# DO_module.net
KiCad netlist of a schematic drawn in EAGLE
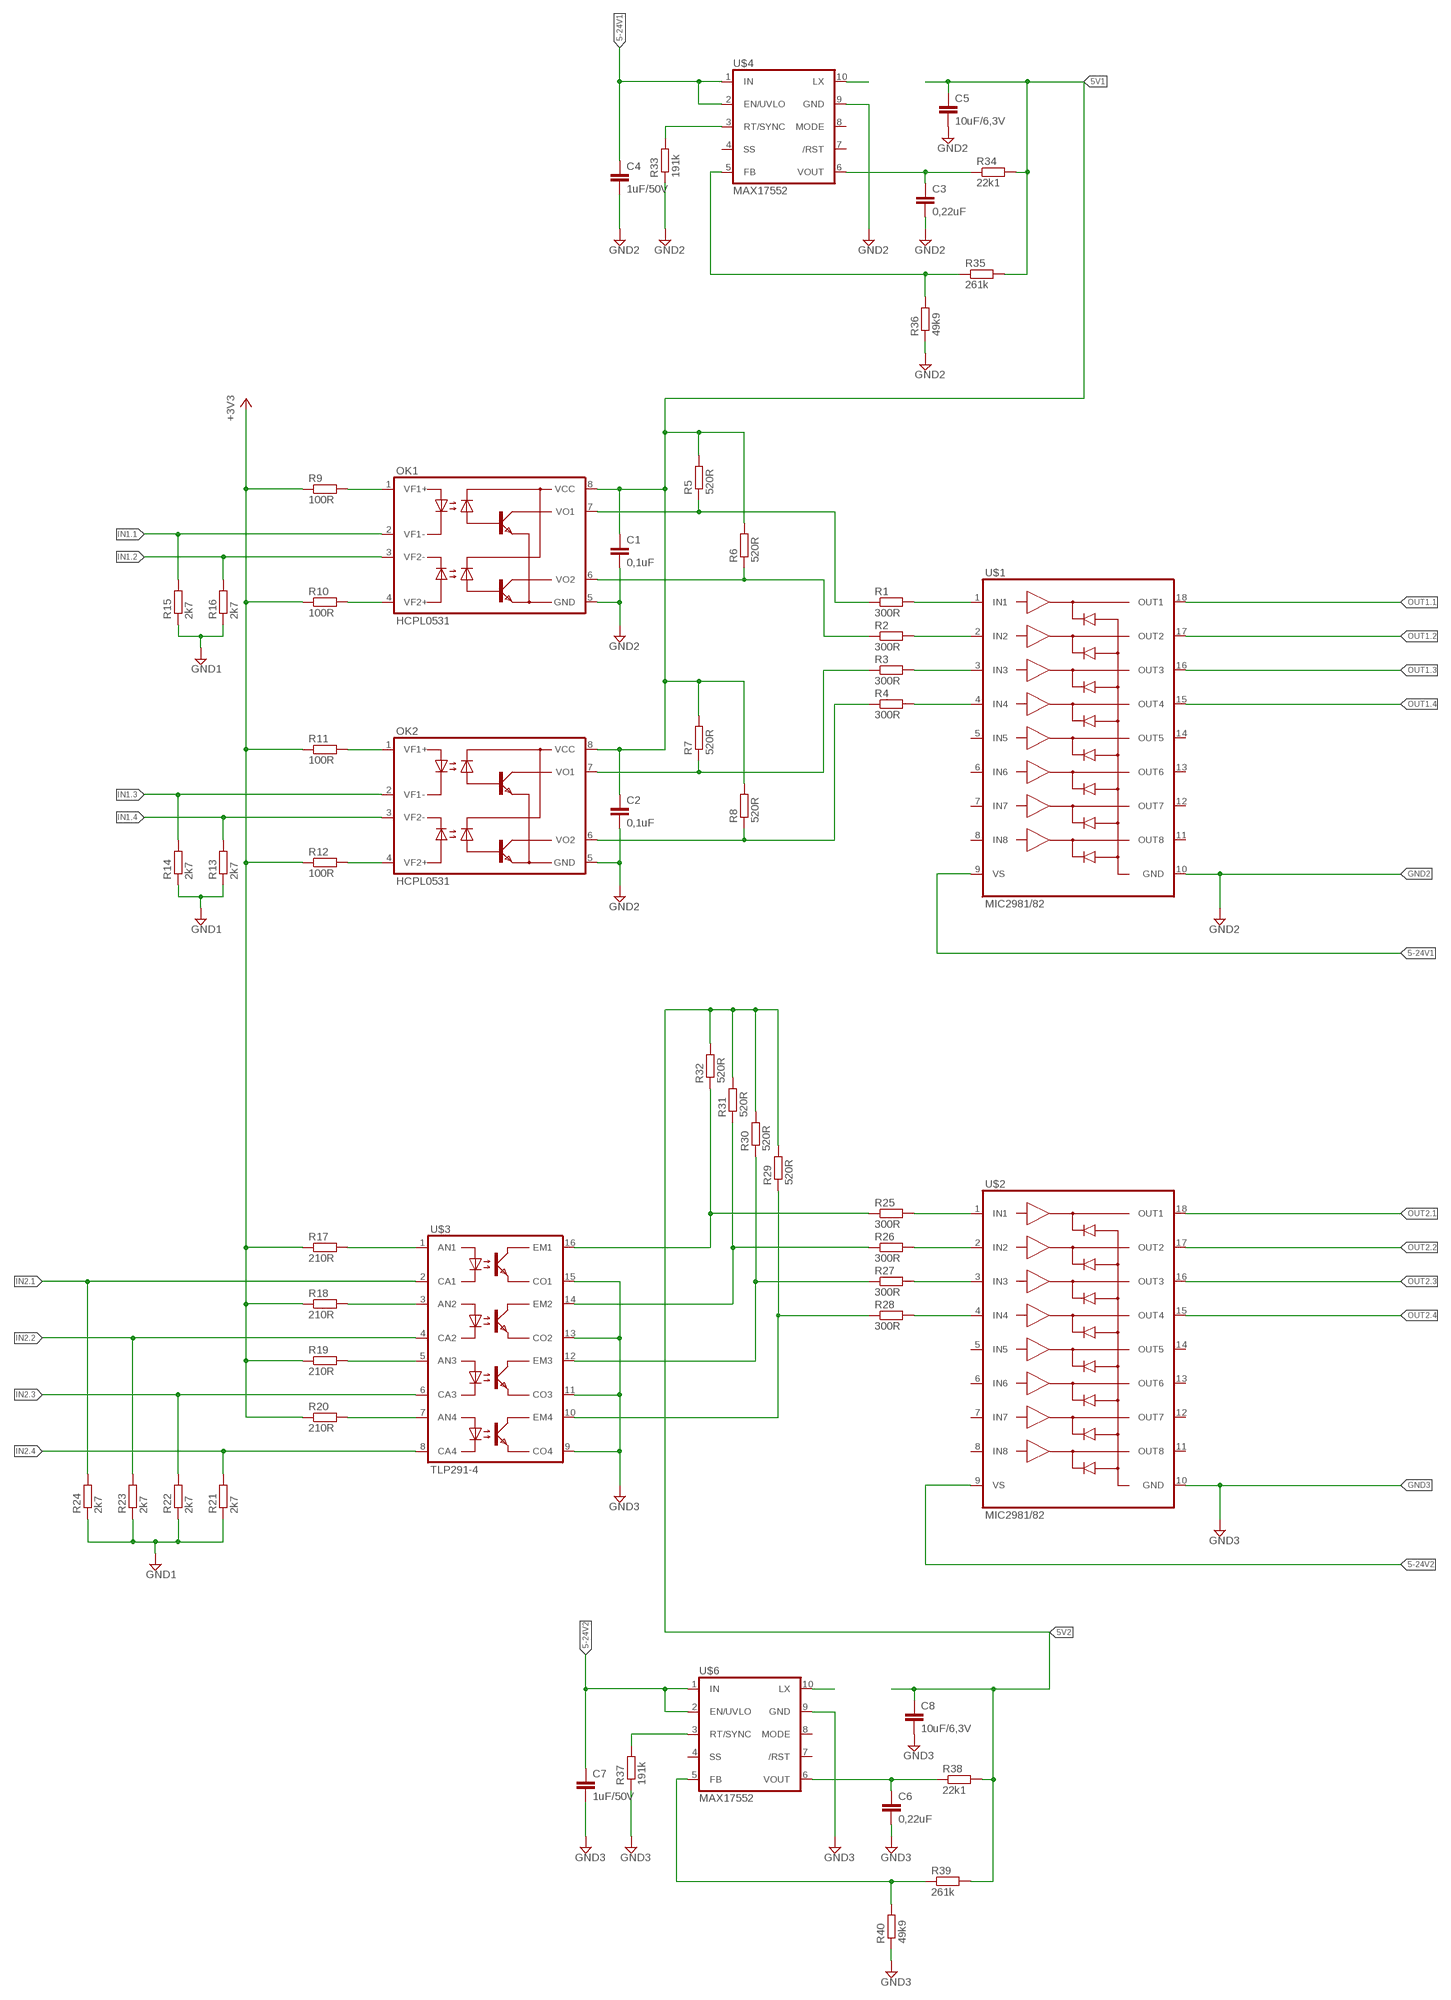
[diagram p0: schematic, sheet 1]

(export (version "E")
  (design (tool "Eeschema 10.0.6"))
  (components
    (comp (ref "C1")
      (value "0,1uF")
      (footprint "eagle-import:C0603")
      (libsource (lib "eagle-import") (part "C-EUC0603"))
    )
    (comp (ref "C2")
      (value "0,1uF")
      (footprint "eagle-import:C0603")
      (libsource (lib "eagle-import") (part "C-EUC0603"))
    )
    (comp (ref "C3")
      (value "0,22uF")
      (footprint "eagle-import:C0603")
      (libsource (lib "eagle-import") (part "C-EUC0603"))
    )
    (comp (ref "C4")
      (value "1uF/50V")
      (footprint "eagle-import:C1206")
      (libsource (lib "eagle-import") (part "C-EUC1206"))
    )
    (comp (ref "C5")
      (value "10uF/6,3V")
      (footprint "eagle-import:C1206")
      (libsource (lib "eagle-import") (part "C-EUC1206"))
    )
    (comp (ref "C6")
      (value "0,22uF")
      (footprint "eagle-import:C0603")
      (libsource (lib "eagle-import") (part "C-EUC0603"))
    )
    (comp (ref "C7")
      (value "1uF/50V")
      (footprint "eagle-import:C1206")
      (libsource (lib "eagle-import") (part "C-EUC1206"))
    )
    (comp (ref "C8")
      (value "10uF/6,3V")
      (footprint "eagle-import:C1206")
      (libsource (lib "eagle-import") (part "C-EUC1206"))
    )
    (comp (ref "OK1")
      (value "HCPL0531")
      (footprint "eagle-import:SOIC08")
      (libsource (lib "eagle-import") (part "HCPL0531"))
    )
    (comp (ref "OK2")
      (value "HCPL0531")
      (footprint "eagle-import:SOIC08")
      (libsource (lib "eagle-import") (part "HCPL0531"))
    )
    (comp (ref "R1")
      (value "300R")
      (footprint "eagle-import:R0603")
      (libsource (lib "eagle-import") (part "R-EU_R0603"))
    )
    (comp (ref "R2")
      (value "300R")
      (footprint "eagle-import:R0603")
      (libsource (lib "eagle-import") (part "R-EU_R0603"))
    )
    (comp (ref "R3")
      (value "300R")
      (footprint "eagle-import:R0603")
      (libsource (lib "eagle-import") (part "R-EU_R0603"))
    )
    (comp (ref "R4")
      (value "300R")
      (footprint "eagle-import:R0603")
      (libsource (lib "eagle-import") (part "R-EU_R0603"))
    )
    (comp (ref "R5")
      (value "520R")
      (footprint "eagle-import:R0603")
      (libsource (lib "eagle-import") (part "R-EU_R0603"))
    )
    (comp (ref "R6")
      (value "520R")
      (footprint "eagle-import:R0603")
      (libsource (lib "eagle-import") (part "R-EU_R0603"))
    )
    (comp (ref "R7")
      (value "520R")
      (footprint "eagle-import:R0603")
      (libsource (lib "eagle-import") (part "R-EU_R0603"))
    )
    (comp (ref "R8")
      (value "520R")
      (footprint "eagle-import:R0603")
      (libsource (lib "eagle-import") (part "R-EU_R0603"))
    )
    (comp (ref "R9")
      (value "100R")
      (footprint "eagle-import:R0603")
      (libsource (lib "eagle-import") (part "R-EU_R0603"))
    )
    (comp (ref "R10")
      (value "100R")
      (footprint "eagle-import:R0603")
      (libsource (lib "eagle-import") (part "R-EU_R0603"))
    )
    (comp (ref "R11")
      (value "100R")
      (footprint "eagle-import:R0603")
      (libsource (lib "eagle-import") (part "R-EU_R0603"))
    )
    (comp (ref "R12")
      (value "100R")
      (footprint "eagle-import:R0603")
      (libsource (lib "eagle-import") (part "R-EU_R0603"))
    )
    (comp (ref "R13")
      (value "2k7")
      (footprint "eagle-import:R0603")
      (libsource (lib "eagle-import") (part "R-EU_R0603"))
    )
    (comp (ref "R14")
      (value "2k7")
      (footprint "eagle-import:R0603")
      (libsource (lib "eagle-import") (part "R-EU_R0603"))
    )
    (comp (ref "R15")
      (value "2k7")
      (footprint "eagle-import:R0603")
      (libsource (lib "eagle-import") (part "R-EU_R0603"))
    )
    (comp (ref "R16")
      (value "2k7")
      (footprint "eagle-import:R0603")
      (libsource (lib "eagle-import") (part "R-EU_R0603"))
    )
    (comp (ref "R17")
      (value "210R")
      (footprint "eagle-import:R0603")
      (libsource (lib "eagle-import") (part "R-EU_R0603"))
    )
    (comp (ref "R18")
      (value "210R")
      (footprint "eagle-import:R0603")
      (libsource (lib "eagle-import") (part "R-EU_R0603"))
    )
    (comp (ref "R19")
      (value "210R")
      (footprint "eagle-import:R0603")
      (libsource (lib "eagle-import") (part "R-EU_R0603"))
    )
    (comp (ref "R20")
      (value "210R")
      (footprint "eagle-import:R0603")
      (libsource (lib "eagle-import") (part "R-EU_R0603"))
    )
    (comp (ref "R21")
      (value "2k7")
      (footprint "eagle-import:R0603")
      (libsource (lib "eagle-import") (part "R-EU_R0603"))
    )
    (comp (ref "R22")
      (value "2k7")
      (footprint "eagle-import:R0603")
      (libsource (lib "eagle-import") (part "R-EU_R0603"))
    )
    (comp (ref "R23")
      (value "2k7")
      (footprint "eagle-import:R0603")
      (libsource (lib "eagle-import") (part "R-EU_R0603"))
    )
    (comp (ref "R24")
      (value "2k7")
      (footprint "eagle-import:R0603")
      (libsource (lib "eagle-import") (part "R-EU_R0603"))
    )
    (comp (ref "R25")
      (value "300R")
      (footprint "eagle-import:R0603")
      (libsource (lib "eagle-import") (part "R-EU_R0603"))
    )
    (comp (ref "R26")
      (value "300R")
      (footprint "eagle-import:R0603")
      (libsource (lib "eagle-import") (part "R-EU_R0603"))
    )
    (comp (ref "R27")
      (value "300R")
      (footprint "eagle-import:R0603")
      (libsource (lib "eagle-import") (part "R-EU_R0603"))
    )
    (comp (ref "R28")
      (value "300R")
      (footprint "eagle-import:R0603")
      (libsource (lib "eagle-import") (part "R-EU_R0603"))
    )
    (comp (ref "R29")
      (value "520R")
      (footprint "eagle-import:R0603")
      (libsource (lib "eagle-import") (part "R-EU_R0603"))
    )
    (comp (ref "R30")
      (value "520R")
      (footprint "eagle-import:R0603")
      (libsource (lib "eagle-import") (part "R-EU_R0603"))
    )
    (comp (ref "R31")
      (value "520R")
      (footprint "eagle-import:R0603")
      (libsource (lib "eagle-import") (part "R-EU_R0603"))
    )
    (comp (ref "R32")
      (value "520R")
      (footprint "eagle-import:R0603")
      (libsource (lib "eagle-import") (part "R-EU_R0603"))
    )
    (comp (ref "R33")
      (value "191k")
      (footprint "eagle-import:R0603")
      (libsource (lib "eagle-import") (part "R-EU_R0603"))
    )
    (comp (ref "R34")
      (value "22k1")
      (footprint "eagle-import:R0603")
      (libsource (lib "eagle-import") (part "R-EU_R0603"))
    )
    (comp (ref "R35")
      (value "261k")
      (footprint "eagle-import:R0603")
      (libsource (lib "eagle-import") (part "R-EU_R0603"))
    )
    (comp (ref "R36")
      (value "49k9")
      (footprint "eagle-import:R0603")
      (libsource (lib "eagle-import") (part "R-EU_R0603"))
    )
    (comp (ref "R37")
      (value "191k")
      (footprint "eagle-import:R0603")
      (libsource (lib "eagle-import") (part "R-EU_R0603"))
    )
    (comp (ref "R38")
      (value "22k1")
      (footprint "eagle-import:R0603")
      (libsource (lib "eagle-import") (part "R-EU_R0603"))
    )
    (comp (ref "R39")
      (value "261k")
      (footprint "eagle-import:R0603")
      (libsource (lib "eagle-import") (part "R-EU_R0603"))
    )
    (comp (ref "R40")
      (value "49k9")
      (footprint "eagle-import:R0603")
      (libsource (lib "eagle-import") (part "R-EU_R0603"))
    )
    (comp (ref "U$1")
      (value "MIC2981/82")
      (footprint "eagle-import:SOP18")
      (libsource (lib "eagle-import") (part "MIC2981/82"))
    )
    (comp (ref "U$2")
      (value "MIC2981/82")
      (footprint "eagle-import:SOP18")
      (libsource (lib "eagle-import") (part "MIC2981/82"))
    )
    (comp (ref "U$3")
      (value "TLP291-4")
      (footprint "eagle-import:SO16")
      (libsource (lib "eagle-import") (part "TLP291-4"))
    )
    (comp (ref "U$4")
      (value "MAX17552")
      (footprint "eagle-import:TSSOP-10(10UMAX)")
      (libsource (lib "eagle-import") (part "MAX17552"))
    )
    (comp (ref "U$6")
      (value "MAX17552")
      (footprint "eagle-import:TSSOP-10(10UMAX)")
      (libsource (lib "eagle-import") (part "MAX17552"))
    )
  )
  (nets
    (net (code "1") (name "+3V3") (class "Default")
      (node (ref "R10") (pin "1") (pinfunction "1_1") (pintype "passive"))
      (node (ref "R11") (pin "1") (pinfunction "1_1") (pintype "passive"))
      (node (ref "R12") (pin "1") (pinfunction "1_1") (pintype "passive"))
      (node (ref "R17") (pin "1") (pinfunction "1_1") (pintype "passive"))
      (node (ref "R18") (pin "1") (pinfunction "1_1") (pintype "passive"))
      (node (ref "R19") (pin "1") (pinfunction "1_1") (pintype "passive"))
      (node (ref "R20") (pin "1") (pinfunction "1_1") (pintype "passive"))
      (node (ref "R9") (pin "1") (pinfunction "1_1") (pintype "passive"))
    )
    (net (code "2") (name "5-24V1") (class "Default")
      (node (ref "C4") (pin "1") (pinfunction "1_1") (pintype "passive"))
      (node (ref "U$1") (pin "9") (pinfunction "VS_9") (pintype "passive"))
      (node (ref "U$4") (pin "1") (pinfunction "IN_1") (pintype "power_in"))
      (node (ref "U$4") (pin "2") (pinfunction "EN/UVLO_2") (pintype "input"))
    )
    (net (code "3") (name "5-24V2") (class "Default")
      (node (ref "C7") (pin "1") (pinfunction "1_1") (pintype "passive"))
      (node (ref "U$2") (pin "9") (pinfunction "VS_9") (pintype "passive"))
      (node (ref "U$6") (pin "1") (pinfunction "IN_1") (pintype "power_in"))
      (node (ref "U$6") (pin "2") (pinfunction "EN/UVLO_2") (pintype "input"))
    )
    (net (code "4") (name "5V1") (class "Default")
      (node (ref "C1") (pin "1") (pinfunction "1_1") (pintype "passive"))
      (node (ref "C2") (pin "1") (pinfunction "1_1") (pintype "passive"))
      (node (ref "C5") (pin "1") (pinfunction "1_1") (pintype "passive"))
      (node (ref "OK1") (pin "8") (pinfunction "VCC_8") (pintype "passive"))
      (node (ref "OK2") (pin "8") (pinfunction "VCC_8") (pintype "passive"))
      (node (ref "R34") (pin "2") (pinfunction "2_2") (pintype "passive"))
      (node (ref "R35") (pin "2") (pinfunction "2_2") (pintype "passive"))
      (node (ref "R5") (pin "2") (pinfunction "2_2") (pintype "passive"))
      (node (ref "R6") (pin "2") (pinfunction "2_2") (pintype "passive"))
      (node (ref "R7") (pin "2") (pinfunction "2_2") (pintype "passive"))
      (node (ref "R8") (pin "2") (pinfunction "2_2") (pintype "passive"))
    )
    (net (code "5") (name "5V2") (class "Default")
      (node (ref "C8") (pin "1") (pinfunction "1_1") (pintype "passive"))
      (node (ref "R29") (pin "2") (pinfunction "2_2") (pintype "passive"))
      (node (ref "R30") (pin "2") (pinfunction "2_2") (pintype "passive"))
      (node (ref "R31") (pin "2") (pinfunction "2_2") (pintype "passive"))
      (node (ref "R32") (pin "2") (pinfunction "2_2") (pintype "passive"))
      (node (ref "R38") (pin "2") (pinfunction "2_2") (pintype "passive"))
      (node (ref "R39") (pin "2") (pinfunction "2_2") (pintype "passive"))
    )
    (net (code "6") (name "GND1") (class "Default")
      (node (ref "R13") (pin "1") (pinfunction "1_1") (pintype "passive"))
      (node (ref "R14") (pin "1") (pinfunction "1_1") (pintype "passive"))
      (node (ref "R15") (pin "1") (pinfunction "1_1") (pintype "passive"))
      (node (ref "R16") (pin "1") (pinfunction "1_1") (pintype "passive"))
      (node (ref "R21") (pin "1") (pinfunction "1_1") (pintype "passive"))
      (node (ref "R22") (pin "1") (pinfunction "1_1") (pintype "passive"))
      (node (ref "R23") (pin "1") (pinfunction "1_1") (pintype "passive"))
      (node (ref "R24") (pin "1") (pinfunction "1_1") (pintype "passive"))
    )
    (net (code "7") (name "GND2") (class "Default")
      (node (ref "C1") (pin "2") (pinfunction "2_2") (pintype "passive"))
      (node (ref "C2") (pin "2") (pinfunction "2_2") (pintype "passive"))
      (node (ref "C3") (pin "2") (pinfunction "2_2") (pintype "passive"))
      (node (ref "C4") (pin "2") (pinfunction "2_2") (pintype "passive"))
      (node (ref "C5") (pin "2") (pinfunction "2_2") (pintype "passive"))
      (node (ref "OK1") (pin "5") (pinfunction "GND_5") (pintype "passive"))
      (node (ref "OK2") (pin "5") (pinfunction "GND_5") (pintype "passive"))
      (node (ref "R33") (pin "1") (pinfunction "1_1") (pintype "passive"))
      (node (ref "R36") (pin "1") (pinfunction "1_1") (pintype "passive"))
      (node (ref "U$1") (pin "10") (pinfunction "GND_10") (pintype "passive"))
      (node (ref "U$4") (pin "9") (pinfunction "GND_9") (pintype "output"))
    )
    (net (code "8") (name "GND3") (class "Default")
      (node (ref "C6") (pin "2") (pinfunction "2_2") (pintype "passive"))
      (node (ref "C7") (pin "2") (pinfunction "2_2") (pintype "passive"))
      (node (ref "C8") (pin "2") (pinfunction "2_2") (pintype "passive"))
      (node (ref "R37") (pin "1") (pinfunction "1_1") (pintype "passive"))
      (node (ref "R40") (pin "1") (pinfunction "1_1") (pintype "passive"))
      (node (ref "U$2") (pin "10") (pinfunction "GND_10") (pintype "passive"))
      (node (ref "U$3") (pin "11") (pinfunction "CO3_11") (pintype "passive"))
      (node (ref "U$3") (pin "13") (pinfunction "CO2_13") (pintype "passive"))
      (node (ref "U$3") (pin "15") (pinfunction "CO1_15") (pintype "passive"))
      (node (ref "U$3") (pin "9") (pinfunction "CO4_9") (pintype "passive"))
      (node (ref "U$6") (pin "9") (pinfunction "GND_9") (pintype "output"))
    )
    (net (code "9") (name "IN1.1") (class "Default")
      (node (ref "OK1") (pin "2") (pinfunction "VF1-_2") (pintype "passive"))
      (node (ref "R15") (pin "2") (pinfunction "2_2") (pintype "passive"))
    )
    (net (code "10") (name "IN1.2") (class "Default")
      (node (ref "OK1") (pin "3") (pinfunction "VF2-_3") (pintype "passive"))
      (node (ref "R16") (pin "2") (pinfunction "2_2") (pintype "passive"))
    )
    (net (code "11") (name "IN1.3") (class "Default")
      (node (ref "OK2") (pin "2") (pinfunction "VF1-_2") (pintype "passive"))
      (node (ref "R14") (pin "2") (pinfunction "2_2") (pintype "passive"))
    )
    (net (code "12") (name "IN1.4") (class "Default")
      (node (ref "OK2") (pin "3") (pinfunction "VF2-_3") (pintype "passive"))
      (node (ref "R13") (pin "2") (pinfunction "2_2") (pintype "passive"))
    )
    (net (code "13") (name "IN2.1") (class "Default")
      (node (ref "R24") (pin "2") (pinfunction "2_2") (pintype "passive"))
      (node (ref "U$3") (pin "2") (pinfunction "CA1_2") (pintype "passive"))
    )
    (net (code "14") (name "IN2.2") (class "Default")
      (node (ref "R23") (pin "2") (pinfunction "2_2") (pintype "passive"))
      (node (ref "U$3") (pin "4") (pinfunction "CA2_4") (pintype "passive"))
    )
    (net (code "15") (name "IN2.3") (class "Default")
      (node (ref "R22") (pin "2") (pinfunction "2_2") (pintype "passive"))
      (node (ref "U$3") (pin "6") (pinfunction "CA3_6") (pintype "passive"))
    )
    (net (code "16") (name "IN2.4") (class "Default")
      (node (ref "R21") (pin "2") (pinfunction "2_2") (pintype "passive"))
      (node (ref "U$3") (pin "8") (pinfunction "CA4_8") (pintype "passive"))
    )
    (net (code "17") (name "Net-(OK1-VF1+)") (class "Default")
      (node (ref "OK1") (pin "1") (pinfunction "VF1+_1") (pintype "passive"))
      (node (ref "R9") (pin "2") (pinfunction "2_2") (pintype "passive"))
    )
    (net (code "18") (name "Net-(OK1-VF2+)") (class "Default")
      (node (ref "OK1") (pin "4") (pinfunction "VF2+_4") (pintype "passive"))
      (node (ref "R10") (pin "2") (pinfunction "2_2") (pintype "passive"))
    )
    (net (code "19") (name "Net-(OK1-VO1)") (class "Default")
      (node (ref "OK1") (pin "7") (pinfunction "VO1_7") (pintype "passive"))
      (node (ref "R1") (pin "1") (pinfunction "1_1") (pintype "passive"))
      (node (ref "R5") (pin "1") (pinfunction "1_1") (pintype "passive"))
    )
    (net (code "20") (name "Net-(OK1-VO2)") (class "Default")
      (node (ref "OK1") (pin "6") (pinfunction "VO2_6") (pintype "passive"))
      (node (ref "R2") (pin "1") (pinfunction "1_1") (pintype "passive"))
      (node (ref "R6") (pin "1") (pinfunction "1_1") (pintype "passive"))
    )
    (net (code "21") (name "Net-(OK2-VF1+)") (class "Default")
      (node (ref "OK2") (pin "1") (pinfunction "VF1+_1") (pintype "passive"))
      (node (ref "R11") (pin "2") (pinfunction "2_2") (pintype "passive"))
    )
    (net (code "22") (name "Net-(OK2-VF2+)") (class "Default")
      (node (ref "OK2") (pin "4") (pinfunction "VF2+_4") (pintype "passive"))
      (node (ref "R12") (pin "2") (pinfunction "2_2") (pintype "passive"))
    )
    (net (code "23") (name "Net-(OK2-VO1)") (class "Default")
      (node (ref "OK2") (pin "7") (pinfunction "VO1_7") (pintype "passive"))
      (node (ref "R3") (pin "1") (pinfunction "1_1") (pintype "passive"))
      (node (ref "R7") (pin "1") (pinfunction "1_1") (pintype "passive"))
    )
    (net (code "24") (name "Net-(OK2-VO2)") (class "Default")
      (node (ref "OK2") (pin "6") (pinfunction "VO2_6") (pintype "passive"))
      (node (ref "R4") (pin "1") (pinfunction "1_1") (pintype "passive"))
      (node (ref "R8") (pin "1") (pinfunction "1_1") (pintype "passive"))
    )
    (net (code "25") (name "Net-(U$1-IN1)") (class "Default")
      (node (ref "R1") (pin "2") (pinfunction "2_2") (pintype "passive"))
      (node (ref "U$1") (pin "1") (pinfunction "IN1_1") (pintype "passive"))
    )
    (net (code "26") (name "Net-(U$1-IN2)") (class "Default")
      (node (ref "R2") (pin "2") (pinfunction "2_2") (pintype "passive"))
      (node (ref "U$1") (pin "2") (pinfunction "IN2_2") (pintype "passive"))
    )
    (net (code "27") (name "Net-(U$1-IN3)") (class "Default")
      (node (ref "R3") (pin "2") (pinfunction "2_2") (pintype "passive"))
      (node (ref "U$1") (pin "3") (pinfunction "IN3_3") (pintype "passive"))
    )
    (net (code "28") (name "Net-(U$1-IN4)") (class "Default")
      (node (ref "R4") (pin "2") (pinfunction "2_2") (pintype "passive"))
      (node (ref "U$1") (pin "4") (pinfunction "IN4_4") (pintype "passive"))
    )
    (net (code "29") (name "Net-(U$2-IN1)") (class "Default")
      (node (ref "R25") (pin "2") (pinfunction "2_2") (pintype "passive"))
      (node (ref "U$2") (pin "1") (pinfunction "IN1_1") (pintype "passive"))
    )
    (net (code "30") (name "Net-(U$2-IN2)") (class "Default")
      (node (ref "R26") (pin "2") (pinfunction "2_2") (pintype "passive"))
      (node (ref "U$2") (pin "2") (pinfunction "IN2_2") (pintype "passive"))
    )
    (net (code "31") (name "Net-(U$2-IN3)") (class "Default")
      (node (ref "R27") (pin "2") (pinfunction "2_2") (pintype "passive"))
      (node (ref "U$2") (pin "3") (pinfunction "IN3_3") (pintype "passive"))
    )
    (net (code "32") (name "Net-(U$2-IN4)") (class "Default")
      (node (ref "R28") (pin "2") (pinfunction "2_2") (pintype "passive"))
      (node (ref "U$2") (pin "4") (pinfunction "IN4_4") (pintype "passive"))
    )
    (net (code "33") (name "Net-(U$3-AN1)") (class "Default")
      (node (ref "R17") (pin "2") (pinfunction "2_2") (pintype "passive"))
      (node (ref "U$3") (pin "1") (pinfunction "AN1_1") (pintype "passive"))
    )
    (net (code "34") (name "Net-(U$3-AN2)") (class "Default")
      (node (ref "R18") (pin "2") (pinfunction "2_2") (pintype "passive"))
      (node (ref "U$3") (pin "3") (pinfunction "AN2_3") (pintype "passive"))
    )
    (net (code "35") (name "Net-(U$3-AN3)") (class "Default")
      (node (ref "R19") (pin "2") (pinfunction "2_2") (pintype "passive"))
      (node (ref "U$3") (pin "5") (pinfunction "AN3_5") (pintype "passive"))
    )
    (net (code "36") (name "Net-(U$3-AN4)") (class "Default")
      (node (ref "R20") (pin "2") (pinfunction "2_2") (pintype "passive"))
      (node (ref "U$3") (pin "7") (pinfunction "AN4_7") (pintype "passive"))
    )
    (net (code "37") (name "Net-(U$3-EM1)") (class "Default")
      (node (ref "R25") (pin "1") (pinfunction "1_1") (pintype "passive"))
      (node (ref "R32") (pin "1") (pinfunction "1_1") (pintype "passive"))
      (node (ref "U$3") (pin "16") (pinfunction "EM1_16") (pintype "passive"))
    )
    (net (code "38") (name "Net-(U$3-EM2)") (class "Default")
      (node (ref "R26") (pin "1") (pinfunction "1_1") (pintype "passive"))
      (node (ref "R31") (pin "1") (pinfunction "1_1") (pintype "passive"))
      (node (ref "U$3") (pin "14") (pinfunction "EM2_14") (pintype "passive"))
    )
    (net (code "39") (name "Net-(U$3-EM3)") (class "Default")
      (node (ref "R27") (pin "1") (pinfunction "1_1") (pintype "passive"))
      (node (ref "R30") (pin "1") (pinfunction "1_1") (pintype "passive"))
      (node (ref "U$3") (pin "12") (pinfunction "EM3_12") (pintype "passive"))
    )
    (net (code "40") (name "Net-(U$3-EM4)") (class "Default")
      (node (ref "R28") (pin "1") (pinfunction "1_1") (pintype "passive"))
      (node (ref "R29") (pin "1") (pinfunction "1_1") (pintype "passive"))
      (node (ref "U$3") (pin "10") (pinfunction "EM4_10") (pintype "passive"))
    )
    (net (code "41") (name "Net-(U$4-FB)") (class "Default")
      (node (ref "R35") (pin "1") (pinfunction "1_1") (pintype "passive"))
      (node (ref "R36") (pin "2") (pinfunction "2_2") (pintype "passive"))
      (node (ref "U$4") (pin "5") (pinfunction "FB_5") (pintype "input"))
    )
    (net (code "42") (name "Net-(U$4-RT{slash}SYNC)") (class "Default")
      (node (ref "R33") (pin "2") (pinfunction "2_2") (pintype "passive"))
      (node (ref "U$4") (pin "3") (pinfunction "RT/SYNC_3") (pintype "input"))
    )
    (net (code "43") (name "Net-(U$4-VOUT)") (class "Default")
      (node (ref "C3") (pin "1") (pinfunction "1_1") (pintype "passive"))
      (node (ref "R34") (pin "1") (pinfunction "1_1") (pintype "passive"))
      (node (ref "U$4") (pin "6") (pinfunction "VOUT_6") (pintype "input"))
    )
    (net (code "44") (name "Net-(U$6-FB)") (class "Default")
      (node (ref "R39") (pin "1") (pinfunction "1_1") (pintype "passive"))
      (node (ref "R40") (pin "2") (pinfunction "2_2") (pintype "passive"))
      (node (ref "U$6") (pin "5") (pinfunction "FB_5") (pintype "input"))
    )
    (net (code "45") (name "Net-(U$6-RT{slash}SYNC)") (class "Default")
      (node (ref "R37") (pin "2") (pinfunction "2_2") (pintype "passive"))
      (node (ref "U$6") (pin "3") (pinfunction "RT/SYNC_3") (pintype "input"))
    )
    (net (code "46") (name "Net-(U$6-VOUT)") (class "Default")
      (node (ref "C6") (pin "1") (pinfunction "1_1") (pintype "passive"))
      (node (ref "R38") (pin "1") (pinfunction "1_1") (pintype "passive"))
      (node (ref "U$6") (pin "6") (pinfunction "VOUT_6") (pintype "input"))
    )
    (net (code "47") (name "OUT1.1") (class "Default")
      (node (ref "U$1") (pin "18") (pinfunction "OUT1_18") (pintype "passive"))
    )
    (net (code "48") (name "OUT1.2") (class "Default")
      (node (ref "U$1") (pin "17") (pinfunction "OUT2_17") (pintype "passive"))
    )
    (net (code "49") (name "OUT1.3") (class "Default")
      (node (ref "U$1") (pin "16") (pinfunction "OUT3_16") (pintype "passive"))
    )
    (net (code "50") (name "OUT1.4") (class "Default")
      (node (ref "U$1") (pin "15") (pinfunction "OUT4_15") (pintype "passive"))
    )
    (net (code "51") (name "OUT2.1") (class "Default")
      (node (ref "U$2") (pin "18") (pinfunction "OUT1_18") (pintype "passive"))
    )
    (net (code "52") (name "OUT2.2") (class "Default")
      (node (ref "U$2") (pin "17") (pinfunction "OUT2_17") (pintype "passive"))
    )
    (net (code "53") (name "OUT2.3") (class "Default")
      (node (ref "U$2") (pin "16") (pinfunction "OUT3_16") (pintype "passive"))
    )
    (net (code "54") (name "OUT2.4") (class "Default")
      (node (ref "U$2") (pin "15") (pinfunction "OUT4_15") (pintype "passive"))
    )
    (net (code "55") (name "unconnected-(U$1-IN5-Pad5)") (class "Default")
      (node (ref "U$1") (pin "5") (pinfunction "IN5_5") (pintype "passive"))
    )
    (net (code "56") (name "unconnected-(U$1-IN6-Pad6)") (class "Default")
      (node (ref "U$1") (pin "6") (pinfunction "IN6_6") (pintype "passive"))
    )
    (net (code "57") (name "unconnected-(U$1-IN7-Pad7)") (class "Default")
      (node (ref "U$1") (pin "7") (pinfunction "IN7_7") (pintype "passive"))
    )
    (net (code "58") (name "unconnected-(U$1-IN8-Pad8)") (class "Default")
      (node (ref "U$1") (pin "8") (pinfunction "IN8_8") (pintype "passive"))
    )
    (net (code "59") (name "unconnected-(U$1-OUT5-Pad14)") (class "Default")
      (node (ref "U$1") (pin "14") (pinfunction "OUT5_14") (pintype "passive"))
    )
    (net (code "60") (name "unconnected-(U$1-OUT6-Pad13)") (class "Default")
      (node (ref "U$1") (pin "13") (pinfunction "OUT6_13") (pintype "passive"))
    )
    (net (code "61") (name "unconnected-(U$1-OUT7-Pad12)") (class "Default")
      (node (ref "U$1") (pin "12") (pinfunction "OUT7_12") (pintype "passive"))
    )
    (net (code "62") (name "unconnected-(U$1-OUT8-Pad11)") (class "Default")
      (node (ref "U$1") (pin "11") (pinfunction "OUT8_11") (pintype "passive"))
    )
    (net (code "63") (name "unconnected-(U$2-IN5-Pad5)") (class "Default")
      (node (ref "U$2") (pin "5") (pinfunction "IN5_5") (pintype "passive"))
    )
    (net (code "64") (name "unconnected-(U$2-IN6-Pad6)") (class "Default")
      (node (ref "U$2") (pin "6") (pinfunction "IN6_6") (pintype "passive"))
    )
    (net (code "65") (name "unconnected-(U$2-IN7-Pad7)") (class "Default")
      (node (ref "U$2") (pin "7") (pinfunction "IN7_7") (pintype "passive"))
    )
    (net (code "66") (name "unconnected-(U$2-IN8-Pad8)") (class "Default")
      (node (ref "U$2") (pin "8") (pinfunction "IN8_8") (pintype "passive"))
    )
    (net (code "67") (name "unconnected-(U$2-OUT5-Pad14)") (class "Default")
      (node (ref "U$2") (pin "14") (pinfunction "OUT5_14") (pintype "passive"))
    )
    (net (code "68") (name "unconnected-(U$2-OUT6-Pad13)") (class "Default")
      (node (ref "U$2") (pin "13") (pinfunction "OUT6_13") (pintype "passive"))
    )
    (net (code "69") (name "unconnected-(U$2-OUT7-Pad12)") (class "Default")
      (node (ref "U$2") (pin "12") (pinfunction "OUT7_12") (pintype "passive"))
    )
    (net (code "70") (name "unconnected-(U$2-OUT8-Pad11)") (class "Default")
      (node (ref "U$2") (pin "11") (pinfunction "OUT8_11") (pintype "passive"))
    )
    (net (code "71") (name "unconnected-(U$4-LX-Pad10)") (class "Default")
      (node (ref "U$4") (pin "10") (pinfunction "LX_10") (pintype "output"))
    )
    (net (code "72") (name "unconnected-(U$4-MODE-Pad8)") (class "Default")
      (node (ref "U$4") (pin "8") (pinfunction "MODE_8") (pintype "input"))
    )
    (net (code "73") (name "unconnected-(U$4-SS-Pad4)") (class "Default")
      (node (ref "U$4") (pin "4") (pinfunction "SS_4") (pintype "input"))
    )
    (net (code "74") (name "unconnected-(U$4-{slash}RST-Pad7)") (class "Default")
      (node (ref "U$4") (pin "7") (pinfunction "/RST_7") (pintype "input"))
    )
    (net (code "75") (name "unconnected-(U$6-LX-Pad10)") (class "Default")
      (node (ref "U$6") (pin "10") (pinfunction "LX_10") (pintype "output"))
    )
    (net (code "76") (name "unconnected-(U$6-MODE-Pad8)") (class "Default")
      (node (ref "U$6") (pin "8") (pinfunction "MODE_8") (pintype "input"))
    )
    (net (code "77") (name "unconnected-(U$6-SS-Pad4)") (class "Default")
      (node (ref "U$6") (pin "4") (pinfunction "SS_4") (pintype "input"))
    )
    (net (code "78") (name "unconnected-(U$6-{slash}RST-Pad7)") (class "Default")
      (node (ref "U$6") (pin "7") (pinfunction "/RST_7") (pintype "input"))
    )
  )
)
